# obc-v2_CM4-PinOut.net
KiCad netlist of a schematic drawn in Altium Designer
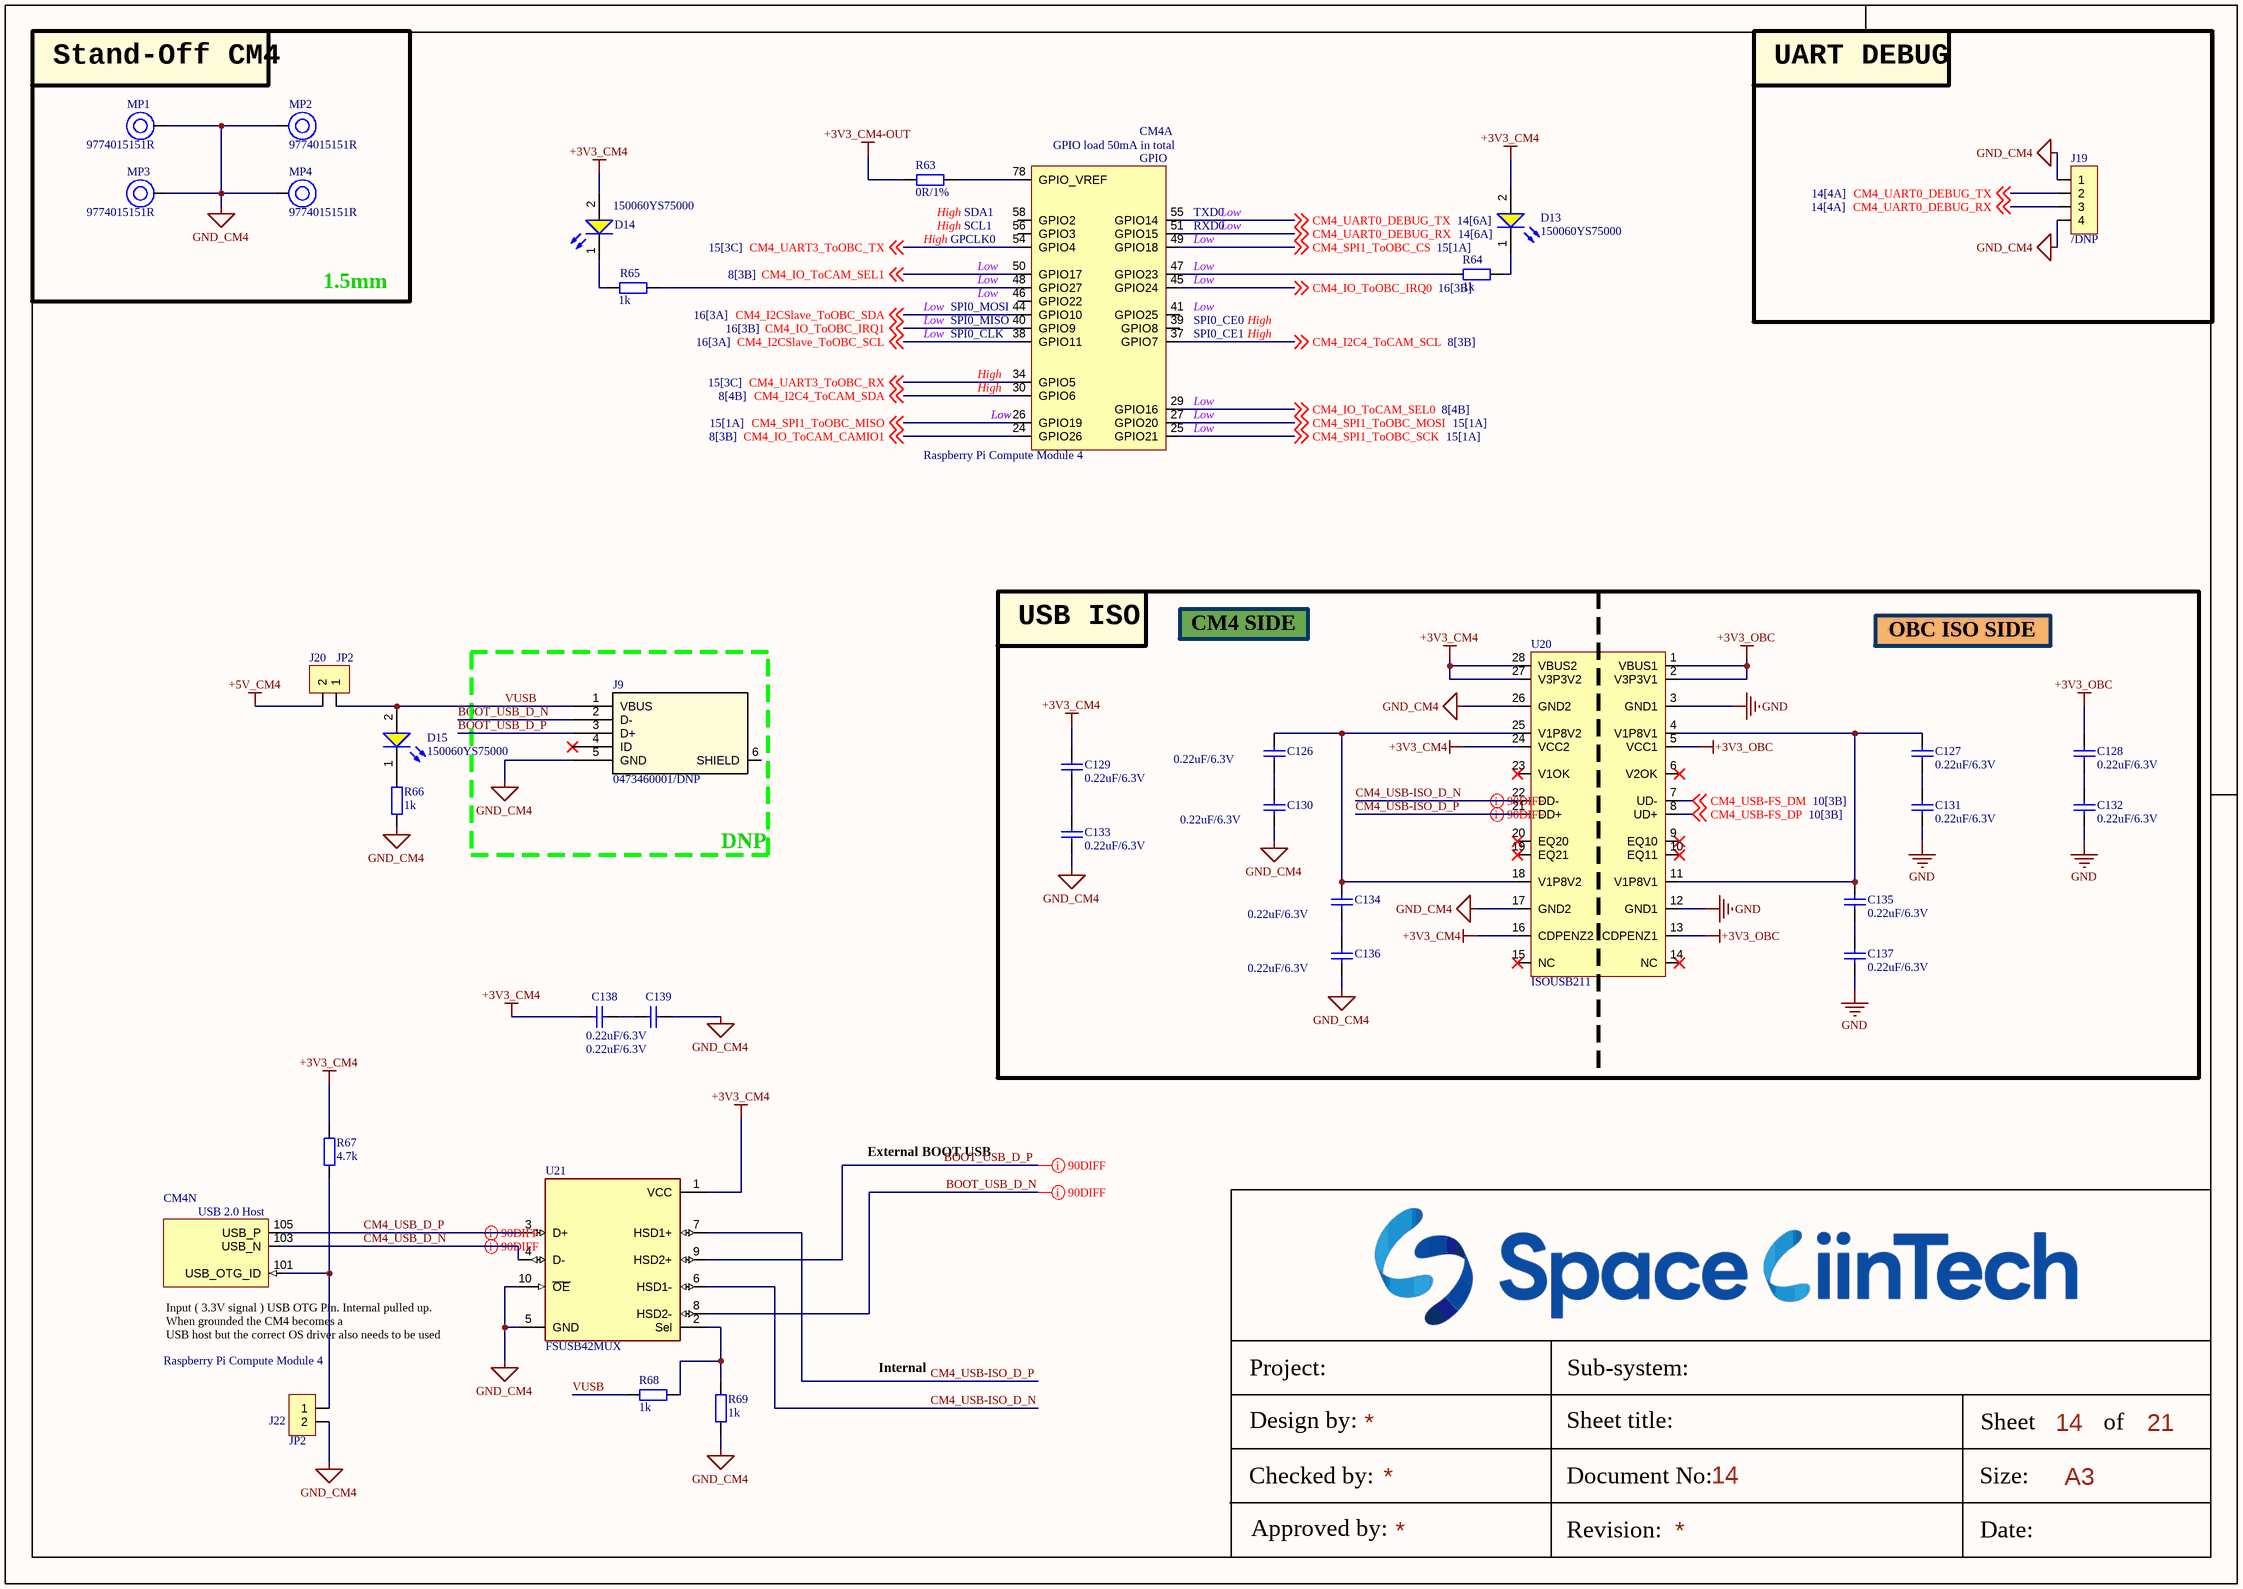
[diagram p0: obc-v2_CM4-PinOut.SchDoc]

(export (version "E")
  (design (tool "Eeschema 10.0.6"))
  (components
    (comp (ref "C126")
      (value "0.22uF/6.3V")
      (footprint "CAP_C_1005X60")
      (description "CAPC")
      (libsource (lib "Altium_Lib_by_KhueNguyenCreator") (part "Tu 0402 33nF 10V"))
    )
    (comp (ref "C127")
      (value "0.22uF/6.3V")
      (footprint "CAP_C_1005X60")
      (description "CAPC")
      (libsource (lib "Altium_Lib_by_KhueNguyenCreator") (part "Tu 0402 33nF 10V"))
    )
    (comp (ref "C128")
      (value "0.22uF/6.3V")
      (footprint "CAP_C_1005X60")
      (description "CAPC")
      (libsource (lib "Altium_Lib_by_KhueNguyenCreator") (part "Tu 0402 33nF 10V"))
    )
    (comp (ref "C129")
      (value "0.22uF/6.3V")
      (footprint "CAP_C_1005X60")
      (description "CAPC")
      (libsource (lib "Altium_Lib_by_KhueNguyenCreator") (part "Tu 0402 33nF 10V"))
    )
    (comp (ref "C130")
      (value "0.22uF/6.3V")
      (footprint "CAP_C_1005X60")
      (description "CAPC")
      (libsource (lib "Altium_Lib_by_KhueNguyenCreator") (part "Tu 0402 33nF 10V"))
    )
    (comp (ref "C131")
      (value "0.22uF/6.3V")
      (footprint "CAP_C_1005X60")
      (description "CAPC")
      (libsource (lib "Altium_Lib_by_KhueNguyenCreator") (part "Tu 0402 33nF 10V"))
    )
    (comp (ref "C132")
      (value "0.22uF/6.3V")
      (footprint "CAP_C_1005X60")
      (description "CAPC")
      (libsource (lib "Altium_Lib_by_KhueNguyenCreator") (part "Tu 0402 33nF 10V"))
    )
    (comp (ref "C133")
      (value "0.22uF/6.3V")
      (footprint "CAP_C_1005X60")
      (description "CAPC")
      (libsource (lib "Altium_Lib_by_KhueNguyenCreator") (part "Tu 0402 33nF 10V"))
    )
    (comp (ref "C134")
      (value "0.22uF/6.3V")
      (footprint "CAP_C_1005X60")
      (description "CAPC")
      (libsource (lib "Altium_Lib_by_KhueNguyenCreator") (part "Tu 0402 33nF 10V"))
    )
    (comp (ref "C135")
      (value "0.22uF/6.3V")
      (footprint "CAP_C_1005X60")
      (description "CAPC")
      (libsource (lib "Altium_Lib_by_KhueNguyenCreator") (part "Tu 0402 33nF 10V"))
    )
    (comp (ref "C136")
      (value "0.22uF/6.3V")
      (footprint "CAP_C_1005X60")
      (description "CAPC")
      (libsource (lib "Altium_Lib_by_KhueNguyenCreator") (part "Tu 0402 33nF 10V"))
    )
    (comp (ref "C137")
      (value "0.22uF/6.3V")
      (footprint "CAP_C_1005X60")
      (description "CAPC")
      (libsource (lib "Altium_Lib_by_KhueNguyenCreator") (part "Tu 0402 33nF 10V"))
    )
    (comp (ref "C138")
      (value "0.22uF/6.3V")
      (footprint "CAP_C_1005X60")
      (description "CAPC")
      (libsource (lib "Altium_Lib_by_KhueNguyenCreator") (part "Tu 0402 33nF 10V"))
    )
    (comp (ref "C139")
      (value "0.22uF/6.3V")
      (footprint "CAP_C_1005X60")
      (description "CAPC")
      (libsource (lib "Altium_Lib_by_KhueNguyenCreator") (part "Tu 0402 33nF 10V"))
    )
    (comp (ref "CM4")
      (value "Raspberry Pi Compute Module 4")
      (footprint "CM4-DF40HC(3.0)-100DS-0.4v_3mm_1.5mm")
      (description "Raspberry Pi Compute Module 4 by Amornthep Phunsin")
      (libsource (lib "CM4") (part "CM4"))
    )
    (comp (ref "D13")
      (value "150060YS75000")
      (footprint "WL-SMCW_0603_150060xx75000")
      (description "LED YELLOW CLEAR 0603 SMD")
      (libsource (lib "Altium Content Vault") (part "LED_Yellow_2A-1K"))
    )
    (comp (ref "D14")
      (value "150060YS75000")
      (footprint "WL-SMCW_0603_150060xx75000")
      (description "LED YELLOW CLEAR 0603 SMD")
      (libsource (lib "Altium Content Vault") (part "LED_Yellow_2A-1K"))
    )
    (comp (ref "D15")
      (value "150060YS75000")
      (footprint "WL-SMCW_0603_150060xx75000")
      (description "LED YELLOW CLEAR 0603 SMD")
      (libsource (lib "Altium Content Vault") (part "LED_Yellow_2A-1K"))
    )
    (comp (ref "J9")
      (value "0473460001/DNP")
      (footprint "47346-0001_MOL")
      (description "No Description Available")
      (libsource (lib "obc_ver2") (part "USB_micro"))
    )
    (comp (ref "J19")
      (value "/DNP")
      (footprint "JP4-C1T")
      (description "WR-PHD 2.54 mm Angled Socket Header")
      (fields
        (field (name "MANUFACTURER") "Würth Elektronik eiSos GmbH")
        (field (name "PARTNO") "613004143121")
        (field (name "CREATED BY") "Karrer Zheng")
      )
      (libsource (lib "TechMT.VN_Lib_Project v2") (part "JP4"))
    )
    (comp (ref "J20")
      (value "JP2")
      (footprint "JP2-D1T")
      (description "WR-PHD 2.54 mm Angled Socket Header")
      (fields
        (field (name "MANUFACTURER") "Würth Elektronik eiSos GmbH")
        (field (name "PARTNO") "613002143121")
        (field (name "CREATED BY") "Karrer Zheng")
      )
      (libsource (lib "") (part "JP2_1"))
    )
    (comp (ref "J22")
      (value "JP2")
      (footprint "JP2-D1T")
      (description "WR-PHD 2.54 mm Angled Socket Header")
      (fields
        (field (name "MANUFACTURER") "Würth Elektronik eiSos GmbH")
        (field (name "PARTNO") "613002143121")
        (field (name "CREATED BY") "Karrer Zheng")
      )
      (libsource (lib "TechMT.VN_Lib") (part "JP2"))
    )
    (comp (ref "MP1")
      (value "9774015151R")
      (footprint "9774015151")
      (description "9774015151R WA-SMSI SMT Steel Spacer, M2.5 Internal non Stop")
      (libsource (lib "Altium Content Vault") (part "Spacer"))
    )
    (comp (ref "MP2")
      (value "9774015151R")
      (footprint "9774015151")
      (description "9774015151R WA-SMSI SMT Steel Spacer, M2.5 Internal non Stop")
      (libsource (lib "Altium Content Vault") (part "Spacer"))
    )
    (comp (ref "MP3")
      (value "9774015151R")
      (footprint "9774015151")
      (description "9774015151R WA-SMSI SMT Steel Spacer, M2.5 Internal non Stop")
      (libsource (lib "Altium Content Vault") (part "Spacer"))
    )
    (comp (ref "MP4")
      (value "9774015151R")
      (footprint "9774015151")
      (description "9774015151R WA-SMSI SMT Steel Spacer, M2.5 Internal non Stop")
      (libsource (lib "Altium Content Vault") (part "Spacer"))
    )
    (comp (ref "R63")
      (value "0R/1%")
      (footprint "RES_C_1608X60")
      (description "RES")
      (libsource (lib "Altium_Lib_by_KhueNguyenCreator") (part "Tro 0603 1% 10k"))
    )
    (comp (ref "R64")
      (value "1k")
      (footprint "RES_C_1608X60")
      (description "RES")
      (libsource (lib "Altium_Lib_by_KhueNguyenCreator") (part "Tro 0603 1% 10k"))
    )
    (comp (ref "R65")
      (value "1k")
      (footprint "RES_C_1608X60")
      (description "RES")
      (libsource (lib "Altium_Lib_by_KhueNguyenCreator") (part "Tro 0603 1% 10k"))
    )
    (comp (ref "R66")
      (value "1k")
      (footprint "RES_C_1608X60")
      (description "RES")
      (libsource (lib "Altium_Lib_by_KhueNguyenCreator") (part "Tro 0603 1% 10k"))
    )
    (comp (ref "R67")
      (value "4.7k")
      (footprint "RES_C_1608X60")
      (description "RES")
      (libsource (lib "Altium_Lib_by_KhueNguyenCreator") (part "Tro 0603 1% 10k"))
    )
    (comp (ref "R68")
      (value "1k")
      (footprint "RES_C_1608X60")
      (description "RES")
      (libsource (lib "Altium_Lib_by_KhueNguyenCreator") (part "Tro 0603 1% 10k"))
    )
    (comp (ref "R69")
      (value "1k")
      (footprint "RES_C_1608X60")
      (description "RES")
      (libsource (lib "Altium_Lib_by_KhueNguyenCreator") (part "Tro 0603 1% 10k"))
    )
    (comp (ref "U20")
      (value "ISOUSB211")
      (footprint "BSSOP_65P_750W_28")
      (libsource (lib "emmc_nofootprint") (part "ISOUSB211"))
    )
    (comp (ref "U21")
      (value "FSUSB42MUX")
      (footprint "FP-846AP-MFG")
      (description "IC USB SWITCH DPDT 10MSOP")
      (fields (field (name "VOLTAGE") "4.3V"))
      (libsource (lib "Altium Content Vault") (part "e0bd5e1b4e0e4edc77f3356c64bf8f9"))
    )
  )
  (nets
    (net (code "1") (name "+3V3_CM4") (class "Default")
      (node (ref "C129") (pin "1") (pinfunction "1_1") (pintype "passive"))
      (node (ref "C138") (pin "1") (pinfunction "1_1") (pintype "passive"))
      (node (ref "D13") (pin "2") (pinfunction "A_2") (pintype "passive"))
      (node (ref "D14") (pin "2") (pinfunction "A_2") (pintype "passive"))
      (node (ref "R67") (pin "1") (pinfunction "1_1") (pintype "passive"))
      (node (ref "U20") (pin "16") (pinfunction "CDPENZ2_16") (pintype "passive"))
      (node (ref "U20") (pin "24") (pinfunction "VCC2_24") (pintype "passive"))
      (node (ref "U20") (pin "27") (pinfunction "V3P3V2_27") (pintype "passive"))
      (node (ref "U20") (pin "28") (pinfunction "VBUS2_28") (pintype "passive"))
      (node (ref "U21") (pin "1") (pinfunction "VCC_1") (pintype "power_in"))
    )
    (net (code "2") (name "+3V3_CM4-OUT") (class "Default")
      (node (ref "R63") (pin "1") (pinfunction "1_1") (pintype "passive"))
    )
    (net (code "3") (name "+3V3_OBC") (class "Default")
      (node (ref "C128") (pin "1") (pinfunction "1_1") (pintype "passive"))
      (node (ref "U20") (pin "1") (pinfunction "VBUS1_1") (pintype "passive"))
      (node (ref "U20") (pin "13") (pinfunction "CDPENZ1_13") (pintype "passive"))
      (node (ref "U20") (pin "2") (pinfunction "V3P3V1_2") (pintype "passive"))
      (node (ref "U20") (pin "5") (pinfunction "VCC1_5") (pintype "passive"))
    )
    (net (code "4") (name "+5V_CM4") (class "Default")
      (node (ref "J20") (pin "2") (pinfunction "2_2") (pintype "passive"))
    )
    (net (code "5") (name "/BOOT_USB_D_N") (class "Default")
      (node (ref "J9") (pin "2") (pinfunction "D-_2") (pintype "passive"))
      (node (ref "U21") (pin "8") (pinfunction "HSD2-_8") (pintype "bidirectional"))
    )
    (net (code "6") (name "/BOOT_USB_D_P") (class "Default")
      (node (ref "J9") (pin "3") (pinfunction "D+_3") (pintype "passive"))
      (node (ref "U21") (pin "9") (pinfunction "HSD2+_9") (pintype "bidirectional"))
    )
    (net (code "7") (name "/CM4_USB-ISO_D_N") (class "Default")
      (node (ref "U20") (pin "22") (pinfunction "DD-_22") (pintype "passive"))
      (node (ref "U21") (pin "6") (pinfunction "HSD1-_6") (pintype "bidirectional"))
    )
    (net (code "8") (name "/CM4_USB-ISO_D_P") (class "Default")
      (node (ref "U20") (pin "21") (pinfunction "DD+_21") (pintype "passive"))
      (node (ref "U21") (pin "7") (pinfunction "HSD1+_7") (pintype "bidirectional"))
    )
    (net (code "9") (name "/CM4_USB_D_N") (class "Default")
      (node (ref "CM4") (pin "103") (pinfunction "USB_N_103") (pintype "passive"))
      (node (ref "U21") (pin "4") (pinfunction "D-_4") (pintype "bidirectional"))
    )
    (net (code "10") (name "/CM4_USB_D_P") (class "Default")
      (node (ref "CM4") (pin "105") (pinfunction "USB_P_105") (pintype "passive"))
      (node (ref "U21") (pin "3") (pinfunction "D+_3") (pintype "bidirectional"))
    )
    (net (code "11") (name "/VUSB") (class "Default")
      (node (ref "D15") (pin "2") (pinfunction "A_2") (pintype "passive"))
      (node (ref "J20") (pin "1") (pinfunction "1_1") (pintype "passive"))
      (node (ref "J9") (pin "1") (pinfunction "VBUS_1") (pintype "passive"))
      (node (ref "R68") (pin "1") (pinfunction "1_1") (pintype "passive"))
    )
    (net (code "12") (name "CM4_I2C4_ToCAM_SCL") (class "Default")
      (node (ref "CM4") (pin "37") (pinfunction "GPIO7_37") (pintype "passive"))
    )
    (net (code "13") (name "CM4_I2C4_ToCAM_SDA") (class "Default")
      (node (ref "CM4") (pin "30") (pinfunction "GPIO6_30") (pintype "passive"))
    )
    (net (code "14") (name "CM4_I2CSlave_ToOBC_SCL") (class "Default")
      (node (ref "CM4") (pin "38") (pinfunction "GPIO11_38") (pintype "passive"))
    )
    (net (code "15") (name "CM4_I2CSlave_ToOBC_SDA") (class "Default")
      (node (ref "CM4") (pin "44") (pinfunction "GPIO10_44") (pintype "passive"))
    )
    (net (code "16") (name "CM4_IO_ToCAM_CAMIO1") (class "Default")
      (node (ref "CM4") (pin "24") (pinfunction "GPIO26_24") (pintype "passive"))
    )
    (net (code "17") (name "CM4_IO_ToCAM_SEL0") (class "Default")
      (node (ref "CM4") (pin "29") (pinfunction "GPIO16_29") (pintype "passive"))
    )
    (net (code "18") (name "CM4_IO_ToCAM_SEL1") (class "Default")
      (node (ref "CM4") (pin "50") (pinfunction "GPIO17_50") (pintype "passive"))
    )
    (net (code "19") (name "CM4_IO_ToOBC_IRQ0") (class "Default")
      (node (ref "CM4") (pin "45") (pinfunction "GPIO24_45") (pintype "passive"))
    )
    (net (code "20") (name "CM4_IO_ToOBC_IRQ1") (class "Default")
      (node (ref "CM4") (pin "40") (pinfunction "GPIO9_40") (pintype "passive"))
    )
    (net (code "21") (name "CM4_SPI1_ToOBC_CS") (class "Default")
      (node (ref "CM4") (pin "49") (pinfunction "GPIO18_49") (pintype "passive"))
    )
    (net (code "22") (name "CM4_SPI1_ToOBC_MISO") (class "Default")
      (node (ref "CM4") (pin "26") (pinfunction "GPIO19_26") (pintype "passive"))
    )
    (net (code "23") (name "CM4_SPI1_ToOBC_MOSI") (class "Default")
      (node (ref "CM4") (pin "27") (pinfunction "GPIO20_27") (pintype "passive"))
    )
    (net (code "24") (name "CM4_SPI1_ToOBC_SCK") (class "Default")
      (node (ref "CM4") (pin "25") (pinfunction "GPIO21_25") (pintype "passive"))
    )
    (net (code "25") (name "CM4_UART0_DEBUG_RX") (class "Default")
      (node (ref "CM4") (pin "51") (pinfunction "GPIO15_51") (pintype "passive"))
      (node (ref "J19") (pin "3") (pinfunction "3_3") (pintype "passive"))
    )
    (net (code "26") (name "CM4_UART0_DEBUG_TX") (class "Default")
      (node (ref "CM4") (pin "55") (pinfunction "GPIO14_55") (pintype "passive"))
      (node (ref "J19") (pin "2") (pinfunction "2_2") (pintype "passive"))
    )
    (net (code "27") (name "CM4_UART3_ToOBC_RX") (class "Default")
      (node (ref "CM4") (pin "34") (pinfunction "GPIO5_34") (pintype "passive"))
    )
    (net (code "28") (name "CM4_UART3_ToOBC_TX") (class "Default")
      (node (ref "CM4") (pin "54") (pinfunction "GPIO4_54") (pintype "passive"))
    )
    (net (code "29") (name "CM4_USB-FS_DM") (class "Default")
      (node (ref "U20") (pin "7") (pinfunction "UD-_7") (pintype "passive"))
    )
    (net (code "30") (name "CM4_USB-FS_DP") (class "Default")
      (node (ref "U20") (pin "8") (pinfunction "UD+_8") (pintype "passive"))
    )
    (net (code "31") (name "GND") (class "Default")
      (node (ref "C131") (pin "2") (pinfunction "2_2") (pintype "passive"))
      (node (ref "C132") (pin "2") (pinfunction "2_2") (pintype "passive"))
      (node (ref "C137") (pin "2") (pinfunction "2_2") (pintype "passive"))
      (node (ref "U20") (pin "12") (pinfunction "GND1_12") (pintype "passive"))
      (node (ref "U20") (pin "3") (pinfunction "GND1_3") (pintype "passive"))
    )
    (net (code "32") (name "GND_CM4") (class "Default")
      (node (ref "C130") (pin "2") (pinfunction "2_2") (pintype "passive"))
      (node (ref "C133") (pin "2") (pinfunction "2_2") (pintype "passive"))
      (node (ref "C136") (pin "2") (pinfunction "2_2") (pintype "passive"))
      (node (ref "C139") (pin "2") (pinfunction "2_2") (pintype "passive"))
      (node (ref "J19") (pin "1") (pinfunction "1_1") (pintype "passive"))
      (node (ref "J19") (pin "4") (pinfunction "4_4") (pintype "passive"))
      (node (ref "J22") (pin "2") (pinfunction "2_2") (pintype "passive"))
      (node (ref "J9") (pin "5") (pinfunction "GND_5") (pintype "power_in"))
      (node (ref "MP1") (pin "1") (pinfunction "1_1") (pintype "passive"))
      (node (ref "MP2") (pin "1") (pinfunction "1_1") (pintype "passive"))
      (node (ref "MP3") (pin "1") (pinfunction "1_1") (pintype "passive"))
      (node (ref "MP4") (pin "1") (pinfunction "1_1") (pintype "passive"))
      (node (ref "R66") (pin "2") (pinfunction "2_2") (pintype "passive"))
      (node (ref "R69") (pin "2") (pinfunction "2_2") (pintype "passive"))
      (node (ref "U20") (pin "17") (pinfunction "GND2_17") (pintype "passive"))
      (node (ref "U20") (pin "26") (pinfunction "GND2_26") (pintype "passive"))
      (node (ref "U21") (pin "10") (pinfunction "~{OE}_10") (pintype "input"))
      (node (ref "U21") (pin "5") (pinfunction "GND_5") (pintype "power_in"))
    )
    (net (code "33") (name "Net-(C126-Pad1)") (class "Default")
      (node (ref "C126") (pin "1") (pinfunction "1_1") (pintype "passive"))
      (node (ref "C134") (pin "1") (pinfunction "1_1") (pintype "passive"))
      (node (ref "U20") (pin "18") (pinfunction "V1P8V2_18") (pintype "passive"))
      (node (ref "U20") (pin "25") (pinfunction "V1P8V2_25") (pintype "passive"))
    )
    (net (code "34") (name "Net-(C126-Pad2)") (class "Default")
      (node (ref "C126") (pin "2") (pinfunction "2_2") (pintype "passive"))
      (node (ref "C130") (pin "1") (pinfunction "1_1") (pintype "passive"))
    )
    (net (code "35") (name "Net-(C127-Pad1)") (class "Default")
      (node (ref "C127") (pin "1") (pinfunction "1_1") (pintype "passive"))
      (node (ref "C135") (pin "1") (pinfunction "1_1") (pintype "passive"))
      (node (ref "U20") (pin "11") (pinfunction "V1P8V1_11") (pintype "passive"))
      (node (ref "U20") (pin "4") (pinfunction "V1P8V1_4") (pintype "passive"))
    )
    (net (code "36") (name "Net-(C127-Pad2)") (class "Default")
      (node (ref "C127") (pin "2") (pinfunction "2_2") (pintype "passive"))
      (node (ref "C131") (pin "1") (pinfunction "1_1") (pintype "passive"))
    )
    (net (code "37") (name "Net-(C128-Pad2)") (class "Default")
      (node (ref "C128") (pin "2") (pinfunction "2_2") (pintype "passive"))
      (node (ref "C132") (pin "1") (pinfunction "1_1") (pintype "passive"))
    )
    (net (code "38") (name "Net-(C129-Pad2)") (class "Default")
      (node (ref "C129") (pin "2") (pinfunction "2_2") (pintype "passive"))
      (node (ref "C133") (pin "1") (pinfunction "1_1") (pintype "passive"))
    )
    (net (code "39") (name "Net-(C134-Pad2)") (class "Default")
      (node (ref "C134") (pin "2") (pinfunction "2_2") (pintype "passive"))
      (node (ref "C136") (pin "1") (pinfunction "1_1") (pintype "passive"))
    )
    (net (code "40") (name "Net-(C135-Pad2)") (class "Default")
      (node (ref "C135") (pin "2") (pinfunction "2_2") (pintype "passive"))
      (node (ref "C137") (pin "1") (pinfunction "1_1") (pintype "passive"))
    )
    (net (code "41") (name "Net-(C138-Pad2)") (class "Default")
      (node (ref "C138") (pin "2") (pinfunction "2_2") (pintype "passive"))
      (node (ref "C139") (pin "1") (pinfunction "1_1") (pintype "passive"))
    )
    (net (code "42") (name "Net-(CM4A-GPIO23)") (class "Default")
      (node (ref "CM4") (pin "47") (pinfunction "GPIO23_47") (pintype "passive"))
      (node (ref "R64") (pin "2") (pinfunction "2_2") (pintype "passive"))
    )
    (net (code "43") (name "Net-(CM4A-GPIO27)") (class "Default")
      (node (ref "CM4") (pin "48") (pinfunction "GPIO27_48") (pintype "passive"))
      (node (ref "R65") (pin "2") (pinfunction "2_2") (pintype "passive"))
    )
    (net (code "44") (name "Net-(CM4A-GPIO_VREF)") (class "Default")
      (node (ref "CM4") (pin "78") (pinfunction "GPIO_VREF_78") (pintype "power_in"))
      (node (ref "R63") (pin "2") (pinfunction "2_2") (pintype "passive"))
    )
    (net (code "45") (name "Net-(CM4N-USB_OTG_ID)") (class "Default")
      (node (ref "CM4") (pin "101") (pinfunction "USB_OTG_ID_101") (pintype "input"))
      (node (ref "J22") (pin "1") (pinfunction "1_1") (pintype "passive"))
      (node (ref "R67") (pin "2") (pinfunction "2_2") (pintype "passive"))
    )
    (net (code "46") (name "Net-(D13-K)") (class "Default")
      (node (ref "D13") (pin "1") (pinfunction "K_1") (pintype "passive"))
      (node (ref "R64") (pin "1") (pinfunction "1_1") (pintype "passive"))
    )
    (net (code "47") (name "Net-(D14-K)") (class "Default")
      (node (ref "D14") (pin "1") (pinfunction "K_1") (pintype "passive"))
      (node (ref "R65") (pin "1") (pinfunction "1_1") (pintype "passive"))
    )
    (net (code "48") (name "Net-(D15-K)") (class "Default")
      (node (ref "D15") (pin "1") (pinfunction "K_1") (pintype "passive"))
      (node (ref "R66") (pin "1") (pinfunction "1_1") (pintype "passive"))
    )
    (net (code "49") (name "Net-(U21-Sel)") (class "Default")
      (node (ref "R68") (pin "2") (pinfunction "2_2") (pintype "passive"))
      (node (ref "R69") (pin "1") (pinfunction "1_1") (pintype "passive"))
      (node (ref "U21") (pin "2") (pinfunction "Sel_2") (pintype "passive"))
    )
    (net (code "50") (name "unconnected-(CM4A-GPIO2-Pad58)") (class "Default")
      (node (ref "CM4") (pin "58") (pinfunction "GPIO2_58") (pintype "passive"))
    )
    (net (code "51") (name "unconnected-(CM4A-GPIO3-Pad56)") (class "Default")
      (node (ref "CM4") (pin "56") (pinfunction "GPIO3_56") (pintype "passive"))
    )
    (net (code "52") (name "unconnected-(CM4A-GPIO8-Pad39)") (class "Default")
      (node (ref "CM4") (pin "39") (pinfunction "GPIO8_39") (pintype "passive"))
    )
    (net (code "53") (name "unconnected-(CM4A-GPIO22-Pad46)") (class "Default")
      (node (ref "CM4") (pin "46") (pinfunction "GPIO22_46") (pintype "passive"))
    )
    (net (code "54") (name "unconnected-(CM4A-GPIO25-Pad41)") (class "Default")
      (node (ref "CM4") (pin "41") (pinfunction "GPIO25_41") (pintype "passive"))
    )
    (net (code "55") (name "unconnected-(J9-ID-Pad4)") (class "Default")
      (node (ref "J9") (pin "4") (pinfunction "ID_4") (pintype "passive+no_connect"))
    )
    (net (code "56") (name "unconnected-(J9-SHIELD-Pad6)") (class "Default")
      (node (ref "J9") (pin "6") (pinfunction "SHIELD_6") (pintype "passive"))
    )
    (net (code "57") (name "unconnected-(U20-EQ10-Pad9)") (class "Default")
      (node (ref "U20") (pin "9") (pinfunction "EQ10_9") (pintype "passive+no_connect"))
    )
    (net (code "58") (name "unconnected-(U20-EQ11-Pad10)") (class "Default")
      (node (ref "U20") (pin "10") (pinfunction "EQ11_10") (pintype "passive+no_connect"))
    )
    (net (code "59") (name "unconnected-(U20-EQ20-Pad20)") (class "Default")
      (node (ref "U20") (pin "20") (pinfunction "EQ20_20") (pintype "passive+no_connect"))
    )
    (net (code "60") (name "unconnected-(U20-EQ21-Pad19)") (class "Default")
      (node (ref "U20") (pin "19") (pinfunction "EQ21_19") (pintype "passive+no_connect"))
    )
    (net (code "61") (name "unconnected-(U20-NC-Pad14)") (class "Default")
      (node (ref "U20") (pin "14") (pinfunction "NC_14") (pintype "passive+no_connect"))
    )
    (net (code "62") (name "unconnected-(U20-NC-Pad15)") (class "Default")
      (node (ref "U20") (pin "15") (pinfunction "NC_15") (pintype "passive+no_connect"))
    )
    (net (code "63") (name "unconnected-(U20-V1OK-Pad23)") (class "Default")
      (node (ref "U20") (pin "23") (pinfunction "V1OK_23") (pintype "passive+no_connect"))
    )
    (net (code "64") (name "unconnected-(U20-V2OK-Pad6)") (class "Default")
      (node (ref "U20") (pin "6") (pinfunction "V2OK_6") (pintype "passive+no_connect"))
    )
  )
)
